# Output-Connectors.net
KiCad netlist of a schematic drawn in Altium Designer
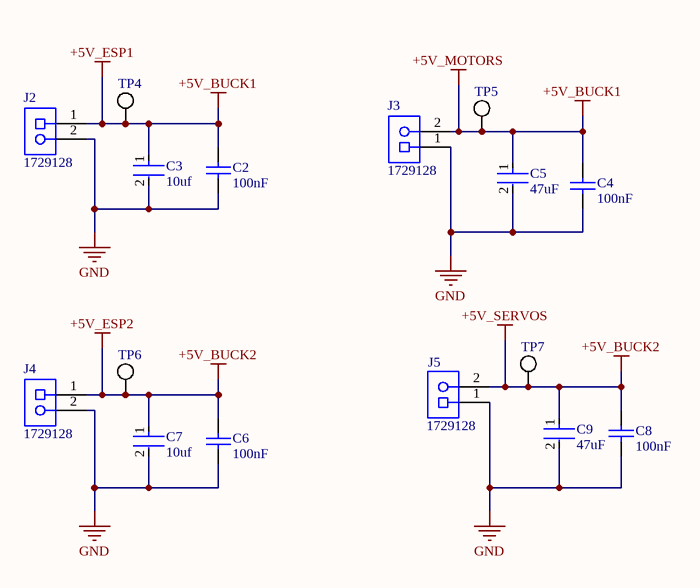
[diagram p0: Output-Connectors.SchDoc]

(export (version "E")
  (design (tool "Eeschema 10.0.6"))
  (components
    (comp (ref "C2")
      (value "100nF")
      (footprint "CAPC1206(3216)170_L")
      (description "CAP 100nF 50V ±10% 1206 (3216 Metric) Thickness 1.7mm SMD")
      (fields (field (name "TOLERANCE") "Â±10%"))
      (libsource (lib "Altium Content Vault") (part "CAP"))
    )
    (comp (ref "C3")
      (value "10uf")
      (footprint "FP-GCJ31C-0_3-IPC_C")
      (description "Cap Ceramic 10uF 10V X7R 10% Pad SMD 1206 Soft Termination  +125°C Automotive T/R")
      (fields (field (name "TOLERANCE") "10%") (field (name "VOLTAGE") "10V"))
      (libsource (lib "Altium Content Vault") (part "b4654b650e69147ec39a6b967a45e02"))
    )
    (comp (ref "C4")
      (value "100nF")
      (footprint "CAPC1206(3216)170_L")
      (description "CAP 100nF 50V ±10% 1206 (3216 Metric) Thickness 1.7mm SMD")
      (fields (field (name "TOLERANCE") "Â±10%"))
      (libsource (lib "Altium Content Vault") (part "CAP"))
    )
    (comp (ref "C5")
      (value "47uF")
      (footprint "FP-1210-L_3_2_0_3-W_2_5_0-IPC_B")
      (description "Capacitor Ceramic Multilayer 47uF 10% 10V X7R SMD 1210")
      (fields (field (name "TOLERANCE") "10%"))
      (libsource (lib "Altium Content Vault") (part "02cd4be3c70576c341d710602a673aa"))
    )
    (comp (ref "C6")
      (value "100nF")
      (footprint "CAPC1206(3216)170_L")
      (description "CAP 100nF 50V ±10% 1206 (3216 Metric) Thickness 1.7mm SMD")
      (fields (field (name "TOLERANCE") "Â±10%"))
      (libsource (lib "Altium Content Vault") (part "CAP"))
    )
    (comp (ref "C7")
      (value "10uf")
      (footprint "FP-GCJ31C-0_3-IPC_C")
      (description "Cap Ceramic 10uF 10V X7R 10% Pad SMD 1206 Soft Termination  +125°C Automotive T/R")
      (fields (field (name "TOLERANCE") "10%") (field (name "VOLTAGE") "10V"))
      (libsource (lib "Altium Content Vault") (part "b4654b650e69147ec39a6b967a45e02"))
    )
    (comp (ref "C8")
      (value "100nF")
      (footprint "CAPC1206(3216)170_L")
      (description "CAP 100nF 50V ±10% 1206 (3216 Metric) Thickness 1.7mm SMD")
      (fields (field (name "TOLERANCE") "Â±10%"))
      (libsource (lib "Altium Content Vault") (part "CAP"))
    )
    (comp (ref "C9")
      (value "47uF")
      (footprint "FP-1210-L_3_2_0_3-W_2_5_0-IPC_B")
      (description "Capacitor Ceramic Multilayer 47uF 10% 10V X7R SMD 1210")
      (fields (field (name "TOLERANCE") "10%"))
      (libsource (lib "Altium Content Vault") (part "02cd4be3c70576c341d710602a673aa"))
    )
    (comp (ref "J2")
      (value "1729128")
      (footprint "PHOE-1729128-2_V")
      (description "PCB Terminal Block, 13.5 A, 400 V, 2-Pin THD, RoHS, Bulk")
      (fields (field (name "MANUFACTURER") "Phoenix Contact"))
      (libsource (lib "Altium Content Vault") (part "CN-2P-F-R2"))
    )
    (comp (ref "J3")
      (value "1729128")
      (footprint "PHOE-1729128-2_V")
      (description "PCB Terminal Block, 13.5 A, 400 V, 2-Pin THD, RoHS, Bulk")
      (fields (field (name "MANUFACTURER") "Phoenix Contact"))
      (libsource (lib "") (part "CN-2P-F-R2_1"))
    )
    (comp (ref "J4")
      (value "1729128")
      (footprint "PHOE-1729128-2_V")
      (description "PCB Terminal Block, 13.5 A, 400 V, 2-Pin THD, RoHS, Bulk")
      (fields (field (name "MANUFACTURER") "Phoenix Contact"))
      (libsource (lib "Altium Content Vault") (part "CN-2P-F-R2"))
    )
    (comp (ref "J5")
      (value "1729128")
      (footprint "PHOE-1729128-2_V")
      (description "PCB Terminal Block, 13.5 A, 400 V, 2-Pin THD, RoHS, Bulk")
      (fields (field (name "MANUFACTURER") "Phoenix Contact"))
      (libsource (lib "") (part "CN-2P-F-R2_1"))
    )
    (comp (ref "TP4")
      (value "Test Point")
      (footprint "Test Point")
      (libsource (lib "University of California, Riverside") (part "Test Point"))
    )
    (comp (ref "TP5")
      (value "Test Point")
      (footprint "Test Point")
      (libsource (lib "University of California, Riverside") (part "Test Point"))
    )
    (comp (ref "TP6")
      (value "Test Point")
      (footprint "Test Point")
      (libsource (lib "University of California, Riverside") (part "Test Point"))
    )
    (comp (ref "TP7")
      (value "Test Point")
      (footprint "Test Point")
      (libsource (lib "University of California, Riverside") (part "Test Point"))
    )
  )
  (nets
    (net (code "1") (name "+5V_BUCK1") (class "Default")
      (node (ref "C2") (pin "2") (pinfunction "2_2") (pintype "passive"))
      (node (ref "C3") (pin "1") (pinfunction "1_1") (pintype "passive"))
      (node (ref "C4") (pin "2") (pinfunction "2_2") (pintype "passive"))
      (node (ref "C5") (pin "1") (pinfunction "1_1") (pintype "passive"))
      (node (ref "J2") (pin "1") (pinfunction "1_1") (pintype "passive"))
      (node (ref "J3") (pin "2") (pinfunction "2_2") (pintype "passive"))
      (node (ref "TP4") (pin "1") (pinfunction "1_1") (pintype "passive"))
      (node (ref "TP5") (pin "1") (pinfunction "1_1") (pintype "passive"))
    )
    (net (code "2") (name "+5V_BUCK2") (class "Default")
      (node (ref "C6") (pin "2") (pinfunction "2_2") (pintype "passive"))
      (node (ref "C7") (pin "1") (pinfunction "1_1") (pintype "passive"))
      (node (ref "C8") (pin "2") (pinfunction "2_2") (pintype "passive"))
      (node (ref "C9") (pin "1") (pinfunction "1_1") (pintype "passive"))
      (node (ref "J4") (pin "1") (pinfunction "1_1") (pintype "passive"))
      (node (ref "J5") (pin "2") (pinfunction "2_2") (pintype "passive"))
      (node (ref "TP6") (pin "1") (pinfunction "1_1") (pintype "passive"))
      (node (ref "TP7") (pin "1") (pinfunction "1_1") (pintype "passive"))
    )
    (net (code "3") (name "GND") (class "Default")
      (node (ref "C2") (pin "1") (pinfunction "1_1") (pintype "passive"))
      (node (ref "C3") (pin "2") (pinfunction "2_2") (pintype "passive"))
      (node (ref "C4") (pin "1") (pinfunction "1_1") (pintype "passive"))
      (node (ref "C5") (pin "2") (pinfunction "2_2") (pintype "passive"))
      (node (ref "C6") (pin "1") (pinfunction "1_1") (pintype "passive"))
      (node (ref "C7") (pin "2") (pinfunction "2_2") (pintype "passive"))
      (node (ref "C8") (pin "1") (pinfunction "1_1") (pintype "passive"))
      (node (ref "C9") (pin "2") (pinfunction "2_2") (pintype "passive"))
      (node (ref "J2") (pin "2") (pinfunction "2_2") (pintype "passive"))
      (node (ref "J3") (pin "1") (pinfunction "1_1") (pintype "passive"))
      (node (ref "J4") (pin "2") (pinfunction "2_2") (pintype "passive"))
      (node (ref "J5") (pin "1") (pinfunction "1_1") (pintype "passive"))
    )
  )
)
